# gowin_vga_ble.net
KiCad netlist of a schematic drawn in Altium Designer
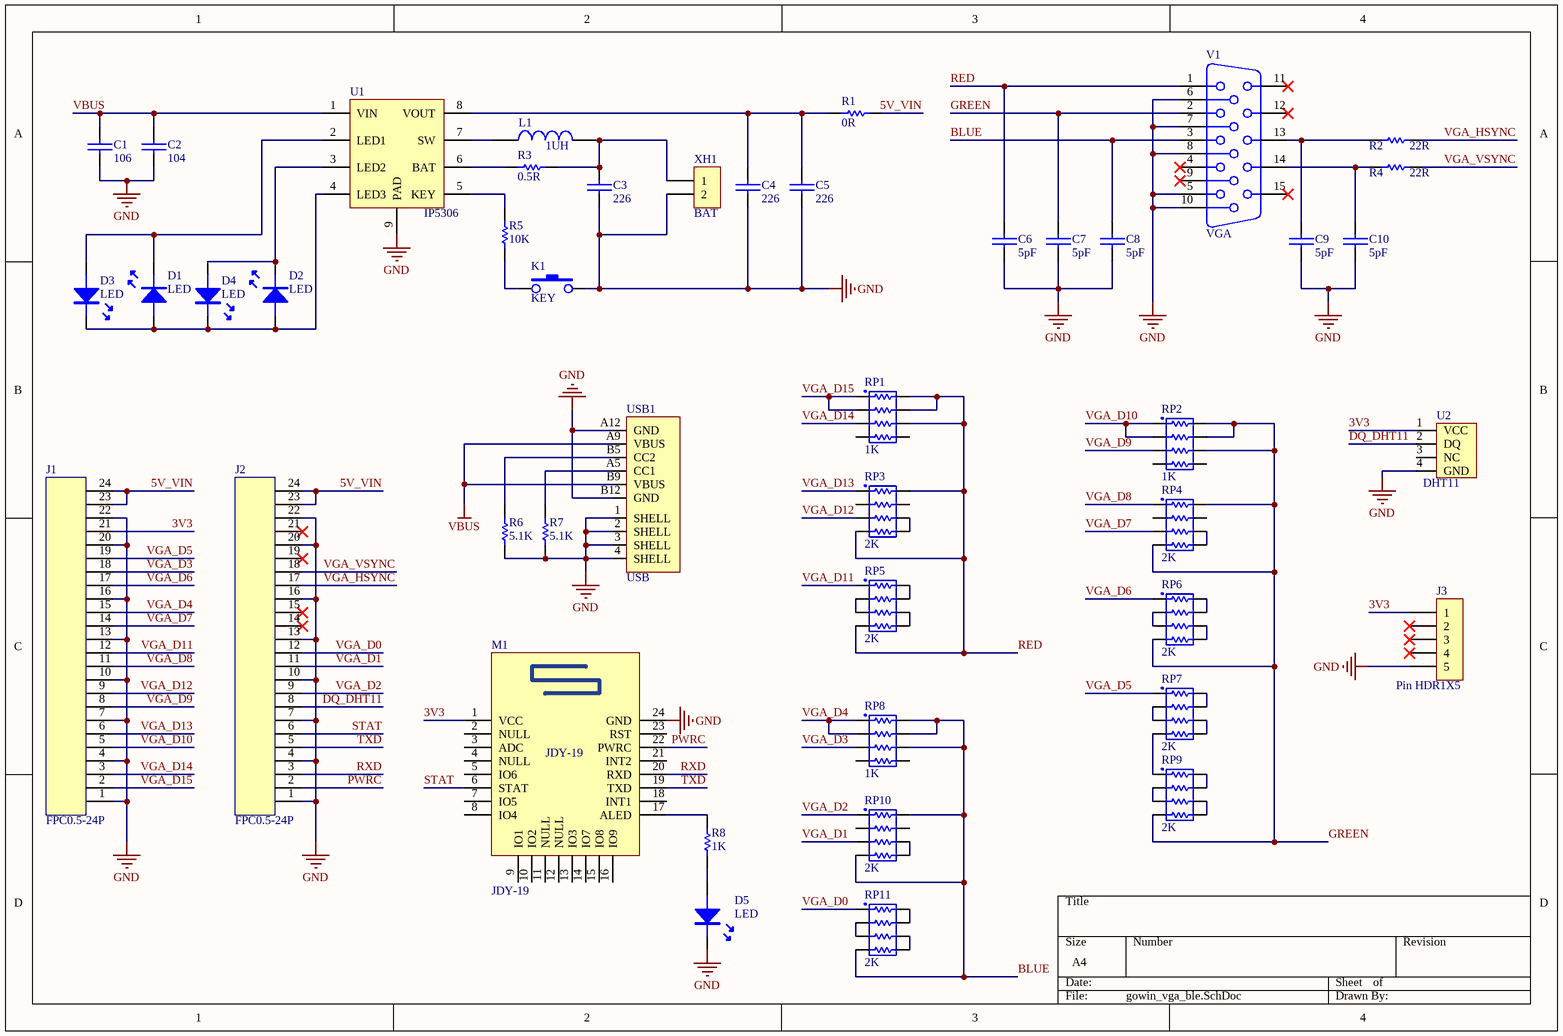
[diagram p0: gowin_vga_ble.SchDoc]

(export (version "E")
  (design (tool "Eeschema 10.0.6"))
  (components
    (comp (ref "C1")
      (value "106")
      (footprint "0603C")
      (description "无极性电容")
      (libsource (lib "电容") (part "CAP"))
    )
    (comp (ref "C2")
      (value "104")
      (footprint "0603C")
      (description "无极性电容")
      (libsource (lib "电容") (part "CAP"))
    )
    (comp (ref "C3")
      (value "226")
      (footprint "0603C")
      (description "无极性电容")
      (libsource (lib "电容") (part "CAP"))
    )
    (comp (ref "C4")
      (value "226")
      (footprint "0603C")
      (description "无极性电容")
      (libsource (lib "电容") (part "CAP"))
    )
    (comp (ref "C5")
      (value "226")
      (footprint "0603C")
      (description "无极性电容")
      (libsource (lib "电容") (part "CAP"))
    )
    (comp (ref "C6")
      (value "5pF")
      (footprint "0603C")
      (description "无极性电容")
      (libsource (lib "电容") (part "CAP"))
    )
    (comp (ref "C7")
      (value "5pF")
      (footprint "0603C")
      (description "无极性电容")
      (libsource (lib "电容") (part "CAP"))
    )
    (comp (ref "C8")
      (value "5pF")
      (footprint "0603C")
      (description "无极性电容")
      (libsource (lib "电容") (part "CAP"))
    )
    (comp (ref "C9")
      (value "5pF")
      (footprint "0603C")
      (description "无极性电容")
      (libsource (lib "电容") (part "CAP"))
    )
    (comp (ref "C10")
      (value "5pF")
      (footprint "0603C")
      (description "无极性电容")
      (libsource (lib "电容") (part "CAP"))
    )
    (comp (ref "D1") (value "LED") (footprint "LED-0603G") (libsource (lib "LED") (part "LED")))
    (comp (ref "D2") (value "LED") (footprint "LED-0603G") (libsource (lib "LED") (part "LED")))
    (comp (ref "D3") (value "LED") (footprint "LED-0603G") (libsource (lib "LED") (part "LED")))
    (comp (ref "D4") (value "LED") (footprint "LED-0603G") (libsource (lib "LED") (part "LED")))
    (comp (ref "D5") (value "LED") (footprint "LED-0603B") (libsource (lib "LED") (part "LED")))
    (comp (ref "J1")
      (value "FPC0.5-24P")
      (footprint "FPC0.5-24P")
      (description "贴片")
      (libsource (lib "FPC") (part "FPC0.5-24P"))
    )
    (comp (ref "J2")
      (value "FPC0.5-24P")
      (footprint "FPC0.5-24P")
      (description "贴片")
      (libsource (lib "FPC") (part "FPC0.5-24P"))
    )
    (comp (ref "J3")
      (value "Pin HDR1X5")
      (footprint "Pin HDR1X5/2.54mm-S")
      (libsource (lib "排针") (part "Pin HDR1X5"))
    )
    (comp (ref "K1") (value "KEY") (footprint "SMD-3X6X4.3") (libsource (lib "轻触开关") (part "KEY")))
    (comp (ref "L1")
      (value "1UH")
      (footprint "0630L")
      (description "INDUCTOR")
      (libsource (lib "电感") (part "INDUCTOR"))
    )
    (comp (ref "M1")
      (value "JDY-19")
      (footprint "Models_Lib:JDY-19")
      (libsource (lib "Models_Lib") (part "JDY-19"))
    )
    (comp (ref "R1") (value "0R") (footprint "0603R") (libsource (lib "电阻") (part "RES")))
    (comp (ref "R2") (value "22R") (footprint "0603R") (libsource (lib "电阻") (part "RES")))
    (comp (ref "R3") (value "0.5R") (footprint "0603R") (libsource (lib "电阻") (part "RES")))
    (comp (ref "R4") (value "22R") (footprint "0603R") (libsource (lib "电阻") (part "RES")))
    (comp (ref "R5") (value "10K") (footprint "0603R") (libsource (lib "电阻") (part "RES")))
    (comp (ref "R6") (value "5.1K") (footprint "0603R") (libsource (lib "电阻") (part "RES")))
    (comp (ref "R7") (value "5.1K") (footprint "0603R") (libsource (lib "电阻") (part "RES")))
    (comp (ref "R8") (value "1K") (footprint "0603R") (libsource (lib "电阻") (part "RES")))
    (comp (ref "RP1") (value "1K") (footprint "贴片排阻") (libsource (lib "电阻") (part "SMT_RES_PACK8")))
    (comp (ref "RP2") (value "1K") (footprint "贴片排阻") (libsource (lib "电阻") (part "SMT_RES_PACK8")))
    (comp (ref "RP3") (value "2K") (footprint "贴片排阻") (libsource (lib "电阻") (part "SMT_RES_PACK8")))
    (comp (ref "RP4") (value "2K") (footprint "贴片排阻") (libsource (lib "电阻") (part "SMT_RES_PACK8")))
    (comp (ref "RP5") (value "2K") (footprint "贴片排阻") (libsource (lib "电阻") (part "SMT_RES_PACK8")))
    (comp (ref "RP6") (value "2K") (footprint "贴片排阻") (libsource (lib "电阻") (part "SMT_RES_PACK8")))
    (comp (ref "RP7") (value "2K") (footprint "贴片排阻") (libsource (lib "电阻") (part "SMT_RES_PACK8")))
    (comp (ref "RP8") (value "1K") (footprint "贴片排阻") (libsource (lib "电阻") (part "SMT_RES_PACK8")))
    (comp (ref "RP9") (value "2K") (footprint "贴片排阻") (libsource (lib "电阻") (part "SMT_RES_PACK8")))
    (comp (ref "RP10") (value "2K") (footprint "贴片排阻") (libsource (lib "电阻") (part "SMT_RES_PACK8")))
    (comp (ref "RP11") (value "2K") (footprint "贴片排阻") (libsource (lib "电阻") (part "SMT_RES_PACK8")))
    (comp (ref "U1") (value "IP5306") (footprint "SOP8-PAD") (libsource (lib "未分类IC") (part "IP5306")))
    (comp (ref "U2")
      (value "DHT11")
      (footprint "DHT11")
      (description "数字温湿度传感器")
      (libsource (lib "PIONEER") (part "DHT11"))
    )
    (comp (ref "USB1") (value "USB") (footprint "USB-C-6PIN") (libsource (lib "USB") (part "USB-C-6PIN")))
    (comp (ref "V1") (value "VGA") (footprint "VGA15/F/90") (libsource (lib "串口") (part "VGA")))
    (comp (ref "XH1") (value "BAT") (footprint "XH2/2.54mm/90") (libsource (lib "XH，VH") (part "XH2")))
  )
  (nets
    (net (code "1") (name "/3V3") (class "Default")
      (node (ref "J1") (pin "21") (pinfunction "21_21") (pintype "passive"))
      (node (ref "J3") (pin "1") (pinfunction "1_1") (pintype "passive"))
      (node (ref "M1") (pin "1") (pinfunction "VCC_1") (pintype "passive"))
      (node (ref "U2") (pin "1") (pinfunction "VCC_1") (pintype "passive"))
    )
    (net (code "2") (name "/5V_VIN") (class "Default")
      (node (ref "J1") (pin "23") (pinfunction "23_23") (pintype "passive"))
      (node (ref "J1") (pin "24") (pinfunction "24_24") (pintype "passive"))
      (node (ref "J2") (pin "23") (pinfunction "23_23") (pintype "passive"))
      (node (ref "J2") (pin "24") (pinfunction "24_24") (pintype "passive"))
      (node (ref "R1") (pin "2") (pinfunction "2_2") (pintype "passive"))
    )
    (net (code "3") (name "/BLUE") (class "Default")
      (node (ref "C8") (pin "2") (pinfunction "2_2") (pintype "passive"))
      (node (ref "RP10") (pin "4") (pinfunction "1_4") (pintype "passive"))
      (node (ref "RP10") (pin "8") (pinfunction "2_8") (pintype "passive"))
      (node (ref "RP11") (pin "4") (pinfunction "1_4") (pintype "passive"))
      (node (ref "RP8") (pin "6") (pinfunction "2_6") (pintype "passive"))
      (node (ref "RP8") (pin "7") (pinfunction "2_7") (pintype "passive"))
      (node (ref "RP8") (pin "8") (pinfunction "2_8") (pintype "passive"))
      (node (ref "V1") (pin "3") (pinfunction "3_3") (pintype "passive"))
    )
    (net (code "4") (name "/DQ_DHT11") (class "Default")
      (node (ref "J2") (pin "8") (pinfunction "8_8") (pintype "passive"))
      (node (ref "U2") (pin "2") (pinfunction "DQ_2") (pintype "passive"))
    )
    (net (code "5") (name "/GREEN") (class "Default")
      (node (ref "C7") (pin "2") (pinfunction "2_2") (pintype "passive"))
      (node (ref "RP2") (pin "6") (pinfunction "2_6") (pintype "passive"))
      (node (ref "RP2") (pin "7") (pinfunction "2_7") (pintype "passive"))
      (node (ref "RP2") (pin "8") (pinfunction "2_8") (pintype "passive"))
      (node (ref "RP4") (pin "4") (pinfunction "1_4") (pintype "passive"))
      (node (ref "RP4") (pin "8") (pinfunction "2_8") (pintype "passive"))
      (node (ref "RP6") (pin "4") (pinfunction "1_4") (pintype "passive"))
      (node (ref "RP9") (pin "4") (pinfunction "1_4") (pintype "passive"))
      (node (ref "V1") (pin "2") (pinfunction "2_2") (pintype "passive"))
    )
    (net (code "6") (name "/PWRC") (class "Default")
      (node (ref "J2") (pin "2") (pinfunction "2_2") (pintype "passive"))
      (node (ref "M1") (pin "22") (pinfunction "PWRC_22") (pintype "passive"))
    )
    (net (code "7") (name "/RED") (class "Default")
      (node (ref "C6") (pin "2") (pinfunction "2_2") (pintype "passive"))
      (node (ref "RP1") (pin "6") (pinfunction "2_6") (pintype "passive"))
      (node (ref "RP1") (pin "7") (pinfunction "2_7") (pintype "passive"))
      (node (ref "RP1") (pin "8") (pinfunction "2_8") (pintype "passive"))
      (node (ref "RP3") (pin "4") (pinfunction "1_4") (pintype "passive"))
      (node (ref "RP3") (pin "8") (pinfunction "2_8") (pintype "passive"))
      (node (ref "RP5") (pin "4") (pinfunction "1_4") (pintype "passive"))
      (node (ref "V1") (pin "1") (pinfunction "1_1") (pintype "passive"))
    )
    (net (code "8") (name "/RXD") (class "Default")
      (node (ref "J2") (pin "3") (pinfunction "3_3") (pintype "passive"))
      (node (ref "M1") (pin "20") (pinfunction "RXD_20") (pintype "passive"))
    )
    (net (code "9") (name "/STAT") (class "Default")
      (node (ref "J2") (pin "6") (pinfunction "6_6") (pintype "passive"))
      (node (ref "M1") (pin "6") (pinfunction "STAT_6") (pintype "passive"))
    )
    (net (code "10") (name "/TXD") (class "Default")
      (node (ref "J2") (pin "5") (pinfunction "5_5") (pintype "passive"))
      (node (ref "M1") (pin "19") (pinfunction "TXD_19") (pintype "passive"))
    )
    (net (code "11") (name "/VGA_D0") (class "Default")
      (node (ref "J2") (pin "12") (pinfunction "12_12") (pintype "passive"))
      (node (ref "RP11") (pin "1") (pinfunction "1_1") (pintype "passive"))
    )
    (net (code "12") (name "/VGA_D1") (class "Default")
      (node (ref "J2") (pin "11") (pinfunction "11_11") (pintype "passive"))
      (node (ref "RP10") (pin "3") (pinfunction "1_3") (pintype "passive"))
    )
    (net (code "13") (name "/VGA_D2") (class "Default")
      (node (ref "J2") (pin "9") (pinfunction "9_9") (pintype "passive"))
      (node (ref "RP10") (pin "1") (pinfunction "1_1") (pintype "passive"))
    )
    (net (code "14") (name "/VGA_D3") (class "Default")
      (node (ref "J1") (pin "18") (pinfunction "18_18") (pintype "passive"))
      (node (ref "RP8") (pin "3") (pinfunction "1_3") (pintype "passive"))
    )
    (net (code "15") (name "/VGA_D4") (class "Default")
      (node (ref "J1") (pin "15") (pinfunction "15_15") (pintype "passive"))
      (node (ref "RP8") (pin "1") (pinfunction "1_1") (pintype "passive"))
      (node (ref "RP8") (pin "2") (pinfunction "1_2") (pintype "passive"))
    )
    (net (code "16") (name "/VGA_D5") (class "Default")
      (node (ref "J1") (pin "19") (pinfunction "19_19") (pintype "passive"))
      (node (ref "RP7") (pin "1") (pinfunction "1_1") (pintype "passive"))
    )
    (net (code "17") (name "/VGA_D6") (class "Default")
      (node (ref "J1") (pin "17") (pinfunction "17_17") (pintype "passive"))
      (node (ref "RP6") (pin "1") (pinfunction "1_1") (pintype "passive"))
    )
    (net (code "18") (name "/VGA_D7") (class "Default")
      (node (ref "J1") (pin "14") (pinfunction "14_14") (pintype "passive"))
      (node (ref "RP4") (pin "3") (pinfunction "1_3") (pintype "passive"))
    )
    (net (code "19") (name "/VGA_D8") (class "Default")
      (node (ref "J1") (pin "11") (pinfunction "11_11") (pintype "passive"))
      (node (ref "RP4") (pin "1") (pinfunction "1_1") (pintype "passive"))
    )
    (net (code "20") (name "/VGA_D9") (class "Default")
      (node (ref "J1") (pin "8") (pinfunction "8_8") (pintype "passive"))
      (node (ref "RP2") (pin "3") (pinfunction "1_3") (pintype "passive"))
    )
    (net (code "21") (name "/VGA_D10") (class "Default")
      (node (ref "J1") (pin "5") (pinfunction "5_5") (pintype "passive"))
      (node (ref "RP2") (pin "1") (pinfunction "1_1") (pintype "passive"))
      (node (ref "RP2") (pin "2") (pinfunction "1_2") (pintype "passive"))
    )
    (net (code "22") (name "/VGA_D11") (class "Default")
      (node (ref "J1") (pin "12") (pinfunction "12_12") (pintype "passive"))
      (node (ref "RP5") (pin "1") (pinfunction "1_1") (pintype "passive"))
    )
    (net (code "23") (name "/VGA_D12") (class "Default")
      (node (ref "J1") (pin "9") (pinfunction "9_9") (pintype "passive"))
      (node (ref "RP3") (pin "3") (pinfunction "1_3") (pintype "passive"))
    )
    (net (code "24") (name "/VGA_D13") (class "Default")
      (node (ref "J1") (pin "6") (pinfunction "6_6") (pintype "passive"))
      (node (ref "RP3") (pin "1") (pinfunction "1_1") (pintype "passive"))
    )
    (net (code "25") (name "/VGA_D14") (class "Default")
      (node (ref "J1") (pin "3") (pinfunction "3_3") (pintype "passive"))
      (node (ref "RP1") (pin "3") (pinfunction "1_3") (pintype "passive"))
    )
    (net (code "26") (name "/VGA_D15") (class "Default")
      (node (ref "J1") (pin "2") (pinfunction "2_2") (pintype "passive"))
      (node (ref "RP1") (pin "1") (pinfunction "1_1") (pintype "passive"))
      (node (ref "RP1") (pin "2") (pinfunction "1_2") (pintype "passive"))
    )
    (net (code "27") (name "/VGA_HSYNC") (class "Default")
      (node (ref "J2") (pin "17") (pinfunction "17_17") (pintype "passive"))
      (node (ref "R2") (pin "2") (pinfunction "2_2") (pintype "passive"))
    )
    (net (code "28") (name "/VGA_VSYNC") (class "Default")
      (node (ref "J2") (pin "18") (pinfunction "18_18") (pintype "passive"))
      (node (ref "R4") (pin "2") (pinfunction "2_2") (pintype "passive"))
    )
    (net (code "29") (name "GND") (class "Default")
      (node (ref "C1") (pin "1") (pinfunction "1_1") (pintype "passive"))
      (node (ref "C10") (pin "1") (pinfunction "1_1") (pintype "passive"))
      (node (ref "C2") (pin "1") (pinfunction "1_1") (pintype "passive"))
      (node (ref "C3") (pin "1") (pinfunction "1_1") (pintype "passive"))
      (node (ref "C4") (pin "1") (pinfunction "1_1") (pintype "passive"))
      (node (ref "C5") (pin "1") (pinfunction "1_1") (pintype "passive"))
      (node (ref "C6") (pin "1") (pinfunction "1_1") (pintype "passive"))
      (node (ref "C7") (pin "1") (pinfunction "1_1") (pintype "passive"))
      (node (ref "C8") (pin "1") (pinfunction "1_1") (pintype "passive"))
      (node (ref "C9") (pin "1") (pinfunction "1_1") (pintype "passive"))
      (node (ref "D5") (pin "K") (pinfunction "K_K") (pintype "passive"))
      (node (ref "J1") (pin "1") (pinfunction "1_1") (pintype "passive"))
      (node (ref "J1") (pin "10") (pinfunction "10_10") (pintype "passive"))
      (node (ref "J1") (pin "13") (pinfunction "13_13") (pintype "passive"))
      (node (ref "J1") (pin "16") (pinfunction "16_16") (pintype "passive"))
      (node (ref "J1") (pin "20") (pinfunction "20_20") (pintype "passive"))
      (node (ref "J1") (pin "22") (pinfunction "22_22") (pintype "passive"))
      (node (ref "J1") (pin "4") (pinfunction "4_4") (pintype "passive"))
      (node (ref "J1") (pin "7") (pinfunction "7_7") (pintype "passive"))
      (node (ref "J2") (pin "1") (pinfunction "1_1") (pintype "passive"))
      (node (ref "J2") (pin "10") (pinfunction "10_10") (pintype "passive"))
      (node (ref "J2") (pin "13") (pinfunction "13_13") (pintype "passive"))
      (node (ref "J2") (pin "16") (pinfunction "16_16") (pintype "passive"))
      (node (ref "J2") (pin "20") (pinfunction "20_20") (pintype "passive"))
      (node (ref "J2") (pin "22") (pinfunction "22_22") (pintype "passive"))
      (node (ref "J2") (pin "4") (pinfunction "4_4") (pintype "passive"))
      (node (ref "J2") (pin "7") (pinfunction "7_7") (pintype "passive"))
      (node (ref "J3") (pin "5") (pinfunction "5_5") (pintype "passive"))
      (node (ref "K1") (pin "3") (pinfunction "3_3") (pintype "passive"))
      (node (ref "M1") (pin "24") (pinfunction "GND_24") (pintype "passive"))
      (node (ref "R6") (pin "2") (pinfunction "2_2") (pintype "passive"))
      (node (ref "R7") (pin "2") (pinfunction "2_2") (pintype "passive"))
      (node (ref "U1") (pin "9") (pinfunction "PAD_9") (pintype "passive"))
      (node (ref "U2") (pin "4") (pinfunction "GND_4") (pintype "passive"))
      (node (ref "USB1") (pin "1") (pinfunction "SHELL_1") (pintype "passive"))
      (node (ref "USB1") (pin "2") (pinfunction "SHELL_2") (pintype "passive"))
      (node (ref "USB1") (pin "3") (pinfunction "SHELL_3") (pintype "passive"))
      (node (ref "USB1") (pin "4") (pinfunction "SHELL_4") (pintype "passive"))
      (node (ref "USB1") (pin "A12") (pinfunction "GND_A12") (pintype "passive"))
      (node (ref "USB1") (pin "B12") (pinfunction "GND_B12") (pintype "passive"))
      (node (ref "V1") (pin "10") (pinfunction "10_10") (pintype "passive"))
      (node (ref "V1") (pin "5") (pinfunction "5_5") (pintype "passive"))
      (node (ref "V1") (pin "6") (pinfunction "6_6") (pintype "passive"))
      (node (ref "V1") (pin "7") (pinfunction "7_7") (pintype "passive"))
      (node (ref "V1") (pin "8") (pinfunction "8_8") (pintype "passive"))
      (node (ref "XH1") (pin "2") (pinfunction "2_2") (pintype "passive"))
    )
    (net (code "30") (name "Net-(C3-Pad2)") (class "Default")
      (node (ref "C3") (pin "2") (pinfunction "2_2") (pintype "passive"))
      (node (ref "L1") (pin "2") (pinfunction "2_2") (pintype "passive"))
      (node (ref "R3") (pin "2") (pinfunction "2_2") (pintype "passive"))
      (node (ref "XH1") (pin "1") (pinfunction "1_1") (pintype "passive"))
    )
    (net (code "31") (name "Net-(C9-Pad2)") (class "Default")
      (node (ref "C9") (pin "2") (pinfunction "2_2") (pintype "passive"))
      (node (ref "R2") (pin "1") (pinfunction "1_1") (pintype "passive"))
      (node (ref "V1") (pin "13") (pinfunction "13_13") (pintype "passive"))
    )
    (net (code "32") (name "Net-(C10-Pad2)") (class "Default")
      (node (ref "C10") (pin "2") (pinfunction "2_2") (pintype "passive"))
      (node (ref "R4") (pin "1") (pinfunction "1_1") (pintype "passive"))
      (node (ref "V1") (pin "14") (pinfunction "14_14") (pintype "passive"))
    )
    (net (code "33") (name "Net-(D5-PadA)") (class "Default")
      (node (ref "D5") (pin "A") (pinfunction "A_A") (pintype "passive"))
      (node (ref "R8") (pin "2") (pinfunction "2_2") (pintype "passive"))
    )
    (net (code "34") (name "Net-(K1-Pad1)") (class "Default")
      (node (ref "K1") (pin "1") (pinfunction "1_1") (pintype "passive"))
      (node (ref "R5") (pin "1") (pinfunction "1_1") (pintype "passive"))
    )
    (net (code "35") (name "Net-(M1-ALED)") (class "Default")
      (node (ref "M1") (pin "17") (pinfunction "ALED_17") (pintype "passive"))
      (node (ref "R8") (pin "1") (pinfunction "1_1") (pintype "passive"))
    )
    (net (code "36") (name "Net-(RP3-2-Pad5)") (class "Default")
      (node (ref "RP3") (pin "5") (pinfunction "2_5") (pintype "passive"))
      (node (ref "RP3") (pin "6") (pinfunction "2_6") (pintype "passive"))
    )
    (net (code "37") (name "Net-(RP4-2-Pad5)") (class "Default")
      (node (ref "RP4") (pin "5") (pinfunction "2_5") (pintype "passive"))
      (node (ref "RP4") (pin "6") (pinfunction "2_6") (pintype "passive"))
    )
    (net (code "38") (name "Net-(RP5-1-Pad2)") (class "Default")
      (node (ref "RP5") (pin "2") (pinfunction "1_2") (pintype "passive"))
      (node (ref "RP5") (pin "3") (pinfunction "1_3") (pintype "passive"))
    )
    (net (code "39") (name "Net-(RP5-2-Pad5)") (class "Default")
      (node (ref "RP5") (pin "5") (pinfunction "2_5") (pintype "passive"))
      (node (ref "RP5") (pin "6") (pinfunction "2_6") (pintype "passive"))
    )
    (net (code "40") (name "Net-(RP5-2-Pad7)") (class "Default")
      (node (ref "RP5") (pin "7") (pinfunction "2_7") (pintype "passive"))
      (node (ref "RP5") (pin "8") (pinfunction "2_8") (pintype "passive"))
    )
    (net (code "41") (name "Net-(RP6-1-Pad2)") (class "Default")
      (node (ref "RP6") (pin "2") (pinfunction "1_2") (pintype "passive"))
      (node (ref "RP6") (pin "3") (pinfunction "1_3") (pintype "passive"))
    )
    (net (code "42") (name "Net-(RP6-2-Pad5)") (class "Default")
      (node (ref "RP6") (pin "5") (pinfunction "2_5") (pintype "passive"))
      (node (ref "RP6") (pin "6") (pinfunction "2_6") (pintype "passive"))
    )
    (net (code "43") (name "Net-(RP6-2-Pad7)") (class "Default")
      (node (ref "RP6") (pin "7") (pinfunction "2_7") (pintype "passive"))
      (node (ref "RP6") (pin "8") (pinfunction "2_8") (pintype "passive"))
    )
    (net (code "44") (name "Net-(RP7-1-Pad2)") (class "Default")
      (node (ref "RP7") (pin "2") (pinfunction "1_2") (pintype "passive"))
      (node (ref "RP7") (pin "3") (pinfunction "1_3") (pintype "passive"))
    )
    (net (code "45") (name "Net-(RP7-1-Pad4)") (class "Default")
      (node (ref "RP7") (pin "4") (pinfunction "1_4") (pintype "passive"))
      (node (ref "RP9") (pin "1") (pinfunction "1_1") (pintype "passive"))
    )
    (net (code "46") (name "Net-(RP7-2-Pad5)") (class "Default")
      (node (ref "RP7") (pin "5") (pinfunction "2_5") (pintype "passive"))
      (node (ref "RP7") (pin "6") (pinfunction "2_6") (pintype "passive"))
    )
    (net (code "47") (name "Net-(RP7-2-Pad7)") (class "Default")
      (node (ref "RP7") (pin "7") (pinfunction "2_7") (pintype "passive"))
      (node (ref "RP7") (pin "8") (pinfunction "2_8") (pintype "passive"))
    )
    (net (code "48") (name "Net-(RP9-1-Pad2)") (class "Default")
      (node (ref "RP9") (pin "2") (pinfunction "1_2") (pintype "passive"))
      (node (ref "RP9") (pin "3") (pinfunction "1_3") (pintype "passive"))
    )
    (net (code "49") (name "Net-(RP9-2-Pad5)") (class "Default")
      (node (ref "RP9") (pin "5") (pinfunction "2_5") (pintype "passive"))
      (node (ref "RP9") (pin "6") (pinfunction "2_6") (pintype "passive"))
    )
    (net (code "50") (name "Net-(RP9-2-Pad7)") (class "Default")
      (node (ref "RP9") (pin "7") (pinfunction "2_7") (pintype "passive"))
      (node (ref "RP9") (pin "8") (pinfunction "2_8") (pintype "passive"))
    )
    (net (code "51") (name "Net-(RP10-2-Pad5)") (class "Default")
      (node (ref "RP10") (pin "5") (pinfunction "2_5") (pintype "passive"))
      (node (ref "RP10") (pin "6") (pinfunction "2_6") (pintype "passive"))
    )
    (net (code "52") (name "Net-(RP11-1-Pad2)") (class "Default")
      (node (ref "RP11") (pin "2") (pinfunction "1_2") (pintype "passive"))
      (node (ref "RP11") (pin "3") (pinfunction "1_3") (pintype "passive"))
    )
    (net (code "53") (name "Net-(RP11-2-Pad5)") (class "Default")
      (node (ref "RP11") (pin "5") (pinfunction "2_5") (pintype "passive"))
      (node (ref "RP11") (pin "6") (pinfunction "2_6") (pintype "passive"))
    )
    (net (code "54") (name "Net-(RP11-2-Pad7)") (class "Default")
      (node (ref "RP11") (pin "7") (pinfunction "2_7") (pintype "passive"))
      (node (ref "RP11") (pin "8") (pinfunction "2_8") (pintype "passive"))
    )
    (net (code "55") (name "Net-(U1-BAT)") (class "Default")
      (node (ref "R3") (pin "1") (pinfunction "1_1") (pintype "passive"))
      (node (ref "U1") (pin "6") (pinfunction "BAT_6") (pintype "passive"))
    )
    (net (code "56") (name "Net-(U1-KEY)") (class "Default")
      (node (ref "R5") (pin "2") (pinfunction "2_2") (pintype "passive"))
      (node (ref "U1") (pin "5") (pinfunction "KEY_5") (pintype "passive"))
    )
    (net (code "57") (name "Net-(U1-LED1)") (class "Default")
      (node (ref "D1") (pin "K") (pinfunction "K_K") (pintype "passive"))
      (node (ref "D3") (pin "A") (pinfunction "A_A") (pintype "passive"))
      (node (ref "U1") (pin "2") (pinfunction "LED1_2") (pintype "passive"))
    )
    (net (code "58") (name "Net-(U1-LED2)") (class "Default")
      (node (ref "D2") (pin "K") (pinfunction "K_K") (pintype "passive"))
      (node (ref "D4") (pin "A") (pinfunction "A_A") (pintype "passive"))
      (node (ref "U1") (pin "3") (pinfunction "LED2_3") (pintype "passive"))
    )
    (net (code "59") (name "Net-(U1-LED3)") (class "Default")
      (node (ref "D1") (pin "A") (pinfunction "A_A") (pintype "passive"))
      (node (ref "D2") (pin "A") (pinfunction "A_A") (pintype "passive"))
      (node (ref "D3") (pin "K") (pinfunction "K_K") (pintype "passive"))
      (node (ref "D4") (pin "K") (pinfunction "K_K") (pintype "passive"))
      (node (ref "U1") (pin "4") (pinfunction "LED3_4") (pintype "passive"))
    )
    (net (code "60") (name "Net-(U1-SW)") (class "Default")
      (node (ref "L1") (pin "1") (pinfunction "1_1") (pintype "passive"))
      (node (ref "U1") (pin "7") (pinfunction "SW_7") (pintype "passive"))
    )
    (net (code "61") (name "Net-(U1-VOUT)") (class "Default")
      (node (ref "C4") (pin "2") (pinfunction "2_2") (pintype "passive"))
      (node (ref "C5") (pin "2") (pinfunction "2_2") (pintype "passive"))
      (node (ref "R1") (pin "1") (pinfunction "1_1") (pintype "passive"))
      (node (ref "U1") (pin "8") (pinfunction "VOUT_8") (pintype "passive"))
    )
    (net (code "62") (name "Net-(USB1-CC1)") (class "Default")
      (node (ref "R7") (pin "1") (pinfunction "1_1") (pintype "passive"))
      (node (ref "USB1") (pin "A5") (pinfunction "CC1_A5") (pintype "passive"))
    )
    (net (code "63") (name "Net-(USB1-CC2)") (class "Default")
      (node (ref "R6") (pin "1") (pinfunction "1_1") (pintype "passive"))
      (node (ref "USB1") (pin "B5") (pinfunction "CC2_B5") (pintype "passive"))
    )
    (net (code "64") (name "VBUS") (class "Default")
      (node (ref "C1") (pin "2") (pinfunction "2_2") (pintype "passive"))
      (node (ref "C2") (pin "2") (pinfunction "2_2") (pintype "passive"))
      (node (ref "U1") (pin "1") (pinfunction "VIN_1") (pintype "passive"))
      (node (ref "USB1") (pin "A9") (pinfunction "VBUS_A9") (pintype "passive"))
      (node (ref "USB1") (pin "B9") (pinfunction "VBUS_B9") (pintype "passive"))
    )
    (net (code "65") (name "unconnected-(J2-Pad14)") (class "Default")
      (node (ref "J2") (pin "14") (pinfunction "14_14") (pintype "passive+no_connect"))
    )
    (net (code "66") (name "unconnected-(J2-Pad15)") (class "Default")
      (node (ref "J2") (pin "15") (pinfunction "15_15") (pintype "passive+no_connect"))
    )
    (net (code "67") (name "unconnected-(J2-Pad19)") (class "Default")
      (node (ref "J2") (pin "19") (pinfunction "19_19") (pintype "passive+no_connect"))
    )
    (net (code "68") (name "unconnected-(J2-Pad21)") (class "Default")
      (node (ref "J2") (pin "21") (pinfunction "21_21") (pintype "passive+no_connect"))
    )
    (net (code "69") (name "unconnected-(J3-Pad2)") (class "Default")
      (node (ref "J3") (pin "2") (pinfunction "2_2") (pintype "passive+no_connect"))
    )
    (net (code "70") (name "unconnected-(J3-Pad3)") (class "Default")
      (node (ref "J3") (pin "3") (pinfunction "3_3") (pintype "passive+no_connect"))
    )
    (net (code "71") (name "unconnected-(J3-Pad4)") (class "Default")
      (node (ref "J3") (pin "4") (pinfunction "4_4") (pintype "passive+no_connect"))
    )
    (net (code "72") (name "unconnected-(M1-ADC-Pad3)") (class "Default")
      (node (ref "M1") (pin "3") (pinfunction "ADC_3") (pintype "passive"))
    )
    (net (code "73") (name "unconnected-(M1-INT1-Pad18)") (class "Default")
      (node (ref "M1") (pin "18") (pinfunction "INT1_18") (pintype "passive"))
    )
    (net (code "74") (name "unconnected-(M1-INT2-Pad21)") (class "Default")
      (node (ref "M1") (pin "21") (pinfunction "INT2_21") (pintype "passive"))
    )
    (net (code "75") (name "unconnected-(M1-IO1-Pad9)") (class "Default")
      (node (ref "M1") (pin "9") (pinfunction "IO1_9") (pintype "passive"))
    )
    (net (code "76") (name "unconnected-(M1-IO2-Pad10)") (class "Default")
      (node (ref "M1") (pin "10") (pinfunction "IO2_10") (pintype "passive"))
    )
    (net (code "77") (name "unconnected-(M1-IO3-Pad13)") (class "Default")
      (node (ref "M1") (pin "13") (pinfunction "IO3_13") (pintype "passive"))
    )
    (net (code "78") (name "unconnected-(M1-IO4-Pad8)") (class "Default")
      (node (ref "M1") (pin "8") (pinfunction "IO4_8") (pintype "passive"))
    )
    (net (code "79") (name "unconnected-(M1-IO5-Pad7)") (class "Default")
      (node (ref "M1") (pin "7") (pinfunction "IO5_7") (pintype "passive"))
    )
    (net (code "80") (name "unconnected-(M1-IO6-Pad5)") (class "Default")
      (node (ref "M1") (pin "5") (pinfunction "IO6_5") (pintype "passive"))
    )
    (net (code "81") (name "unconnected-(M1-IO7-Pad14)") (class "Default")
      (node (ref "M1") (pin "14") (pinfunction "IO7_14") (pintype "passive"))
    )
    (net (code "82") (name "unconnected-(M1-IO8-Pad15)") (class "Default")
      (node (ref "M1") (pin "15") (pinfunction "IO8_15") (pintype "passive"))
    )
    (net (code "83") (name "unconnected-(M1-IO9-Pad16)") (class "Default")
      (node (ref "M1") (pin "16") (pinfunction "IO9_16") (pintype "passive"))
    )
    (net (code "84") (name "unconnected-(M1-NULL-Pad2)") (class "Default")
      (node (ref "M1") (pin "2") (pinfunction "NULL_2") (pintype "passive"))
    )
    (net (code "85") (name "unconnected-(M1-NULL-Pad4)") (class "Default")
      (node (ref "M1") (pin "4") (pinfunction "NULL_4") (pintype "passive"))
    )
    (net (code "86") (name "unconnected-(M1-NULL-Pad11)") (class "Default")
      (node (ref "M1") (pin "11") (pinfunction "NULL_11") (pintype "passive"))
    )
    (net (code "87") (name "unconnected-(M1-NULL-Pad12)") (class "Default")
      (node (ref "M1") (pin "12") (pinfunction "NULL_12") (pintype "passive"))
    )
    (net (code "88") (name "unconnected-(M1-RST-Pad23)") (class "Default")
      (node (ref "M1") (pin "23") (pinfunction "RST_23") (pintype "passive"))
    )
    (net (code "89") (name "unconnected-(RP1-1-Pad4)") (class "Default")
      (node (ref "RP1") (pin "4") (pinfunction "1_4") (pintype "passive"))
    )
    (net (code "90") (name "unconnected-(RP1-2-Pad5)") (class "Default")
      (node (ref "RP1") (pin "5") (pinfunction "2_5") (pintype "passive"))
    )
    (net (code "91") (name "unconnected-(RP2-1-Pad4)") (class "Default")
      (node (ref "RP2") (pin "4") (pinfunction "1_4") (pintype "passive"))
    )
    (net (code "92") (name "unconnected-(RP2-2-Pad5)") (class "Default")
      (node (ref "RP2") (pin "5") (pinfunction "2_5") (pintype "passive"))
    )
    (net (code "93") (name "unconnected-(RP3-1-Pad2)") (class "Default")
      (node (ref "RP3") (pin "2") (pinfunction "1_2") (pintype "passive"))
    )
    (net (code "94") (name "unconnected-(RP3-2-Pad7)") (class "Default")
      (node (ref "RP3") (pin "7") (pinfunction "2_7") (pintype "passive"))
    )
    (net (code "95") (name "unconnected-(RP4-1-Pad2)") (class "Default")
      (node (ref "RP4") (pin "2") (pinfunction "1_2") (pintype "passive"))
    )
    (net (code "96") (name "unconnected-(RP4-2-Pad7)") (class "Default")
      (node (ref "RP4") (pin "7") (pinfunction "2_7") (pintype "passive"))
    )
    (net (code "97") (name "unconnected-(RP8-1-Pad4)") (class "Default")
      (node (ref "RP8") (pin "4") (pinfunction "1_4") (pintype "passive"))
    )
    (net (code "98") (name "unconnected-(RP8-2-Pad5)") (class "Default")
      (node (ref "RP8") (pin "5") (pinfunction "2_5") (pintype "passive"))
    )
    (net (code "99") (name "unconnected-(RP10-1-Pad2)") (class "Default")
      (node (ref "RP10") (pin "2") (pinfunction "1_2") (pintype "passive"))
    )
    (net (code "100") (name "unconnected-(RP10-2-Pad7)") (class "Default")
      (node (ref "RP10") (pin "7") (pinfunction "2_7") (pintype "passive"))
    )
    (net (code "101") (name "unconnected-(U2-NC-Pad3)") (class "Default")
      (node (ref "U2") (pin "3") (pinfunction "NC_3") (pintype "passive"))
    )
    (net (code "102") (name "unconnected-(V1-Pad4)") (class "Default")
      (node (ref "V1") (pin "4") (pinfunction "4_4") (pintype "passive+no_connect"))
    )
    (net (code "103") (name "unconnected-(V1-Pad9)") (class "Default")
      (node (ref "V1") (pin "9") (pinfunction "9_9") (pintype "passive+no_connect"))
    )
    (net (code "104") (name "unconnected-(V1-Pad11)") (class "Default")
      (node (ref "V1") (pin "11") (pinfunction "11_11") (pintype "passive+no_connect"))
    )
    (net (code "105") (name "unconnected-(V1-Pad12)") (class "Default")
      (node (ref "V1") (pin "12") (pinfunction "12_12") (pintype "passive+no_connect"))
    )
    (net (code "106") (name "unconnected-(V1-Pad15)") (class "Default")
      (node (ref "V1") (pin "15") (pinfunction "15_15") (pintype "passive+no_connect"))
    )
  )
)
